# weko.net
KiCad netlist of a schematic drawn in EAGLE
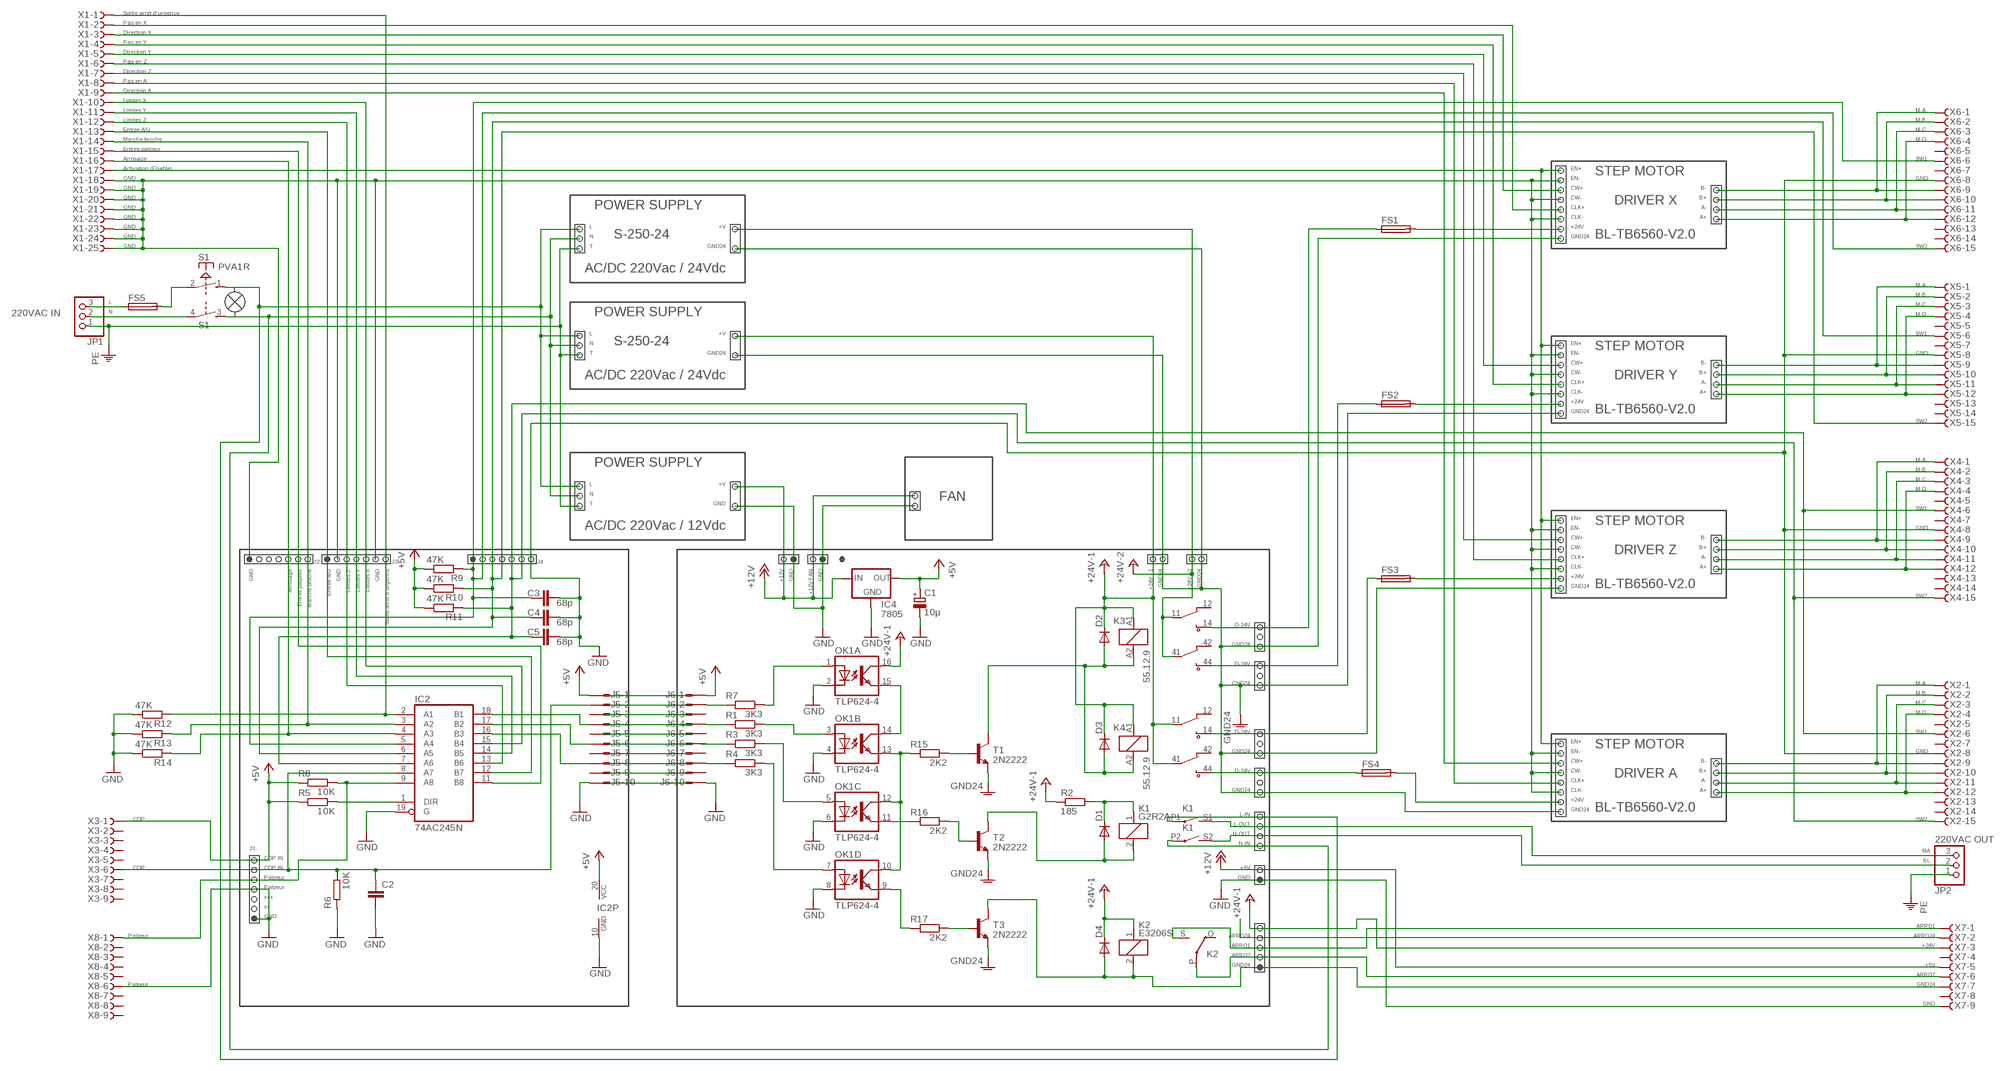
[diagram p0: schematic, sheet 1]

(export (version "E")
  (design (tool "Eeschema 10.0.6"))
  (components
    (comp (ref "C1")
      (value "10µ")
      (footprint "eagle-import:E2-4")
      (libsource (lib "eagle-import") (part "CPOL-EUE2-4"))
    )
    (comp (ref "C2")
      (value "C-EU050-030X075")
      (footprint "eagle-import:C050-030X075")
      (libsource (lib "eagle-import") (part "C-EU050-030X075"))
    )
    (comp (ref "C3")
      (value "68p")
      (footprint "eagle-import:C050-030X075")
      (libsource (lib "eagle-import") (part "C-EU050-030X075"))
    )
    (comp (ref "C4")
      (value "68p")
      (footprint "eagle-import:C050-030X075")
      (libsource (lib "eagle-import") (part "C-EU050-030X075"))
    )
    (comp (ref "C5")
      (value "68p")
      (footprint "eagle-import:C050-030X075")
      (libsource (lib "eagle-import") (part "C-EU050-030X075"))
    )
    (comp (ref "D1")
      (value "1N4148DO35-10")
      (footprint "eagle-import:DO35-10")
      (libsource (lib "eagle-import") (part "1N4148DO35-10"))
    )
    (comp (ref "D2")
      (value "1N4148DO35-10")
      (footprint "eagle-import:DO35-10")
      (libsource (lib "eagle-import") (part "1N4148DO35-10"))
    )
    (comp (ref "D3")
      (value "1N4148DO35-10")
      (footprint "eagle-import:DO35-10")
      (libsource (lib "eagle-import") (part "1N4148DO35-10"))
    )
    (comp (ref "D4")
      (value "1N4148DO35-10")
      (footprint "eagle-import:DO35-10")
      (libsource (lib "eagle-import") (part "1N4148DO35-10"))
    )
    (comp (ref "FS1")
      (value "KS10H")
      (footprint "eagle-import:KS10H")
      (libsource (lib "eagle-import") (part "KS10H"))
    )
    (comp (ref "FS2")
      (value "KS10H")
      (footprint "eagle-import:KS10H")
      (libsource (lib "eagle-import") (part "KS10H"))
    )
    (comp (ref "FS3")
      (value "KS10H")
      (footprint "eagle-import:KS10H")
      (libsource (lib "eagle-import") (part "KS10H"))
    )
    (comp (ref "FS4")
      (value "KS10H")
      (footprint "eagle-import:KS10H")
      (libsource (lib "eagle-import") (part "KS10H"))
    )
    (comp (ref "FS5")
      (value "KS10H")
      (footprint "eagle-import:KS10H")
      (libsource (lib "eagle-import") (part "KS10H"))
    )
    (comp (ref "IC2")
      (value "74AC245N")
      (footprint "eagle-import:DIL20")
      (libsource (lib "eagle-import") (part "74245NAC"))
    )
    (comp (ref "IC4")
      (value "7805")
      (footprint "eagle-import:78MXXS")
      (libsource (lib "eagle-import") (part "78MXXS"))
    )
    (comp (ref "J5")
      (value "10HS")
      (footprint "eagle-import:10H")
      (libsource (lib "eagle-import") (part "10HS"))
    )
    (comp (ref "J6")
      (value "10HS")
      (footprint "eagle-import:10H")
      (libsource (lib "eagle-import") (part "10HS"))
    )
    (comp (ref "JP1")
      (value "PINHD-1X03_2.00")
      (footprint "eagle-import:1X03M")
      (libsource (lib "eagle-import") (part "PINHD-1X03_2.00"))
    )
    (comp (ref "JP2")
      (value "PINHD-1X03_2.00")
      (footprint "eagle-import:1X03M")
      (libsource (lib "eagle-import") (part "PINHD-1X03_2.00"))
    )
    (comp (ref "K1")
      (value "G2R2A")
      (footprint "eagle-import:G2R2A")
      (fields (field (name "MPN") "G2R-2A-DC24"))
      (libsource (lib "eagle-import") (part "G2R2A"))
    )
    (comp (ref "K2")
      (value "E3206S")
      (footprint "eagle-import:E3206S")
      (libsource (lib "eagle-import") (part "E3206S"))
    )
    (comp (ref "K3")
      (value "55.12.9")
      (footprint "eagle-import:55.12")
      (libsource (lib "eagle-import") (part "55.12.8"))
    )
    (comp (ref "K4")
      (value "55.12.9")
      (footprint "eagle-import:55.12")
      (libsource (lib "eagle-import") (part "55.12.8"))
    )
    (comp (ref "OK1")
      (value "TLP624-4")
      (footprint "eagle-import:MINI-FLAT-16")
      (libsource (lib "eagle-import") (part "TLP283-4"))
    )
    (comp (ref "R1")
      (value "3K3")
      (footprint "eagle-import:0411_12")
      (libsource (lib "eagle-import") (part "R-EU_0411/12"))
    )
    (comp (ref "R2")
      (value "185")
      (footprint "eagle-import:0411_12")
      (libsource (lib "eagle-import") (part "R-EU_0411/12"))
    )
    (comp (ref "R3")
      (value "3K3")
      (footprint "eagle-import:0411_12")
      (libsource (lib "eagle-import") (part "R-EU_0411/12"))
    )
    (comp (ref "R4")
      (value "3K3")
      (footprint "eagle-import:0411_12")
      (libsource (lib "eagle-import") (part "R-EU_0411/12"))
    )
    (comp (ref "R5")
      (value "10K")
      (footprint "eagle-import:0411_12")
      (libsource (lib "eagle-import") (part "R-EU_0411/12"))
    )
    (comp (ref "R6")
      (value "10K")
      (footprint "eagle-import:0411_12")
      (libsource (lib "eagle-import") (part "R-EU_0411/12"))
    )
    (comp (ref "R7")
      (value "3K3")
      (footprint "eagle-import:0411_12")
      (libsource (lib "eagle-import") (part "R-EU_0411/12"))
    )
    (comp (ref "R8")
      (value "10K")
      (footprint "eagle-import:0411_12")
      (libsource (lib "eagle-import") (part "R-EU_0411/12"))
    )
    (comp (ref "R9")
      (value "47K")
      (footprint "eagle-import:0411_12")
      (libsource (lib "eagle-import") (part "R-EU_0411/12"))
    )
    (comp (ref "R10")
      (value "47K")
      (footprint "eagle-import:0411_12")
      (libsource (lib "eagle-import") (part "R-EU_0411/12"))
    )
    (comp (ref "R11")
      (value "47K")
      (footprint "eagle-import:0411_12")
      (libsource (lib "eagle-import") (part "R-EU_0411/12"))
    )
    (comp (ref "R12")
      (value "47K")
      (footprint "eagle-import:0411_12")
      (libsource (lib "eagle-import") (part "R-EU_0411/12"))
    )
    (comp (ref "R13")
      (value "47K")
      (footprint "eagle-import:0411_12")
      (libsource (lib "eagle-import") (part "R-EU_0411/12"))
    )
    (comp (ref "R14")
      (value "47K")
      (footprint "eagle-import:0411_12")
      (libsource (lib "eagle-import") (part "R-EU_0411/12"))
    )
    (comp (ref "R15")
      (value "2K2")
      (footprint "eagle-import:0411_12")
      (libsource (lib "eagle-import") (part "R-EU_0411/12"))
    )
    (comp (ref "R16")
      (value "2K2")
      (footprint "eagle-import:0411_12")
      (libsource (lib "eagle-import") (part "R-EU_0411/12"))
    )
    (comp (ref "R17")
      (value "2K2")
      (footprint "eagle-import:0411_12")
      (libsource (lib "eagle-import") (part "R-EU_0411/12"))
    )
    (comp (ref "S1")
      (value "PVA1R")
      (footprint "eagle-import:PVA1R")
      (libsource (lib "eagle-import") (part "PVA1R"))
    )
    (comp (ref "T1")
      (value "2N2222")
      (footprint "eagle-import:TO18")
      (libsource (lib "eagle-import") (part "2N2222"))
    )
    (comp (ref "T2")
      (value "2N2222")
      (footprint "eagle-import:TO18")
      (libsource (lib "eagle-import") (part "2N2222"))
    )
    (comp (ref "T3")
      (value "2N2222")
      (footprint "eagle-import:TO18")
      (libsource (lib "eagle-import") (part "2N2222"))
    )
    (comp (ref "X1")
      (value "F25VBS")
      (footprint "eagle-import:F25VB")
      (libsource (lib "eagle-import") (part "F25?SVB"))
    )
    (comp (ref "X2")
      (value "F15VBS")
      (footprint "eagle-import:F15VB")
      (libsource (lib "eagle-import") (part "F15?SVB"))
    )
    (comp (ref "X3")
      (value "F09VBS")
      (footprint "eagle-import:F09VB")
      (libsource (lib "eagle-import") (part "F09?SVB"))
    )
    (comp (ref "X4")
      (value "F15VBS")
      (footprint "eagle-import:F15VB")
      (libsource (lib "eagle-import") (part "F15?SVB"))
    )
    (comp (ref "X5")
      (value "F15VBS")
      (footprint "eagle-import:F15VB")
      (libsource (lib "eagle-import") (part "F15?SVB"))
    )
    (comp (ref "X6")
      (value "F15VBS")
      (footprint "eagle-import:F15VB")
      (libsource (lib "eagle-import") (part "F15?SVB"))
    )
    (comp (ref "X7")
      (value "F09VBS")
      (footprint "eagle-import:F09VB")
      (libsource (lib "eagle-import") (part "F09?SVB"))
    )
    (comp (ref "X8")
      (value "F09VBS")
      (footprint "eagle-import:F09VB")
      (libsource (lib "eagle-import") (part "F09?SVB"))
    )
  )
  (nets
    (net (code "1") (name "+5V") (class "Default")
      (node (ref "C1") (pin "+") (pinfunction "+_+") (pintype "passive"))
      (node (ref "IC2") (pin "20") (pinfunction "VCC_20") (pintype "power_in"))
      (node (ref "IC4") (pin "OUT") (pinfunction "OUT_OUT") (pintype "passive"))
      (node (ref "J5") (pin "1") (pinfunction "S_1") (pintype "passive"))
      (node (ref "J6") (pin "1") (pinfunction "S_1") (pintype "passive"))
      (node (ref "R10") (pin "1") (pinfunction "1_1") (pintype "passive"))
      (node (ref "R11") (pin "1") (pinfunction "1_1") (pintype "passive"))
      (node (ref "R5") (pin "2") (pinfunction "2_2") (pintype "passive"))
      (node (ref "R8") (pin "2") (pinfunction "2_2") (pintype "passive"))
      (node (ref "R9") (pin "1") (pinfunction "1_1") (pintype "passive"))
      (node (ref "X3") (pin "1") (pinfunction "F_1") (pintype "passive"))
    )
    (net (code "2") (name "+12V") (class "Default")
      (node (ref "IC4") (pin "IN") (pinfunction "IN_IN") (pintype "input"))
      (node (ref "X7") (pin "5") (pinfunction "F_5") (pintype "passive"))
    )
    (net (code "3") (name "+24V-1") (class "Default")
      (node (ref "D2") (pin "C") (pinfunction "C_C") (pintype "passive"))
      (node (ref "D3") (pin "C") (pinfunction "C_C") (pintype "passive"))
      (node (ref "D4") (pin "C") (pinfunction "C_C") (pintype "passive"))
      (node (ref "K2") (pin "1") (pinfunction "1_1") (pintype "passive"))
      (node (ref "K3") (pin "11") (pinfunction "9_11") (pintype "passive"))
      (node (ref "K3") (pin "41") (pinfunction "12_41") (pintype "passive"))
      (node (ref "K3") (pin "A1") (pinfunction "A1_A1") (pintype "passive"))
      (node (ref "K4") (pin "11") (pinfunction "9_11") (pintype "passive"))
      (node (ref "K4") (pin "41") (pinfunction "12_41") (pintype "passive"))
      (node (ref "K4") (pin "A1") (pinfunction "A1_A1") (pintype "passive"))
      (node (ref "OK1") (pin "16") (pinfunction "COL_16") (pintype "passive"))
      (node (ref "R2") (pin "1") (pinfunction "1_1") (pintype "passive"))
      (node (ref "X7") (pin "3") (pinfunction "F_3") (pintype "passive"))
    )
    (net (code "4") (name "GND") (class "Default")
      (node (ref "C1") (pin "-") (pinfunction "-_-") (pintype "passive"))
      (node (ref "C2") (pin "2") (pinfunction "2_2") (pintype "passive"))
      (node (ref "C3") (pin "2") (pinfunction "2_2") (pintype "passive"))
      (node (ref "C4") (pin "2") (pinfunction "2_2") (pintype "passive"))
      (node (ref "C5") (pin "2") (pinfunction "2_2") (pintype "passive"))
      (node (ref "IC2") (pin "10") (pinfunction "GND_10") (pintype "power_in"))
      (node (ref "IC2") (pin "19") (pinfunction "G_19") (pintype "input"))
      (node (ref "IC4") (pin "GND") (pinfunction "GND_GND") (pintype "input"))
      (node (ref "J5") (pin "10") (pinfunction "S_10") (pintype "passive"))
      (node (ref "J6") (pin "10") (pinfunction "S_10") (pintype "passive"))
      (node (ref "OK1") (pin "2") (pinfunction "C_2") (pintype "passive"))
      (node (ref "OK1") (pin "4") (pinfunction "C_4") (pintype "passive"))
      (node (ref "OK1") (pin "6") (pinfunction "C_6") (pintype "passive"))
      (node (ref "OK1") (pin "8") (pinfunction "C_8") (pintype "passive"))
      (node (ref "R12") (pin "1") (pinfunction "1_1") (pintype "passive"))
      (node (ref "R13") (pin "1") (pinfunction "1_1") (pintype "passive"))
      (node (ref "R14") (pin "1") (pinfunction "1_1") (pintype "passive"))
      (node (ref "R6") (pin "2") (pinfunction "2_2") (pintype "passive"))
      (node (ref "X2") (pin "8") (pinfunction "F_8") (pintype "passive"))
      (node (ref "X4") (pin "8") (pinfunction "F_8") (pintype "passive"))
      (node (ref "X5") (pin "8") (pinfunction "F_8") (pintype "passive"))
      (node (ref "X6") (pin "8") (pinfunction "F_8") (pintype "passive"))
      (node (ref "X7") (pin "9") (pinfunction "F_9") (pintype "passive"))
      (node (ref "X8") (pin "6") (pinfunction "F_6") (pintype "passive"))
    )
    (net (code "5") (name "GND24") (class "Default")
      (node (ref "T1") (pin "1") (pinfunction "E_1") (pintype "passive"))
      (node (ref "T2") (pin "1") (pinfunction "E_1") (pintype "passive"))
      (node (ref "T3") (pin "1") (pinfunction "E_1") (pintype "passive"))
    )
    (net (code "6") (name "Net-(D1-PadC)") (class "Default")
      (node (ref "D1") (pin "C") (pinfunction "C_C") (pintype "passive"))
      (node (ref "K1") (pin "1") (pinfunction "1_1") (pintype "passive"))
      (node (ref "R2") (pin "2") (pinfunction "2_2") (pintype "passive"))
    )
    (net (code "7") (name "Net-(FS5-Pad1)") (class "Default")
      (node (ref "FS5") (pin "1") (pinfunction "1_1") (pintype "passive"))
      (node (ref "JP1") (pin "3") (pinfunction "3_3") (pintype "passive"))
    )
    (net (code "8") (name "Net-(IC2A-A1)") (class "Default")
      (node (ref "IC2") (pin "2") (pinfunction "A1_2") (pintype "bidirectional"))
      (node (ref "R12") (pin "2") (pinfunction "2_2") (pintype "passive"))
      (node (ref "X1") (pin "1") (pinfunction "F_1") (pintype "passive"))
    )
    (net (code "9") (name "Net-(IC2A-A2)") (class "Default")
      (node (ref "IC2") (pin "3") (pinfunction "A2_3") (pintype "bidirectional"))
      (node (ref "R13") (pin "2") (pinfunction "2_2") (pintype "passive"))
      (node (ref "X1") (pin "14") (pinfunction "F_14") (pintype "passive"))
    )
    (net (code "10") (name "Net-(IC2A-A3)") (class "Default")
      (node (ref "IC2") (pin "4") (pinfunction "A3_4") (pintype "bidirectional"))
      (node (ref "R14") (pin "2") (pinfunction "2_2") (pintype "passive"))
      (node (ref "X1") (pin "16") (pinfunction "F_16") (pintype "passive"))
    )
    (net (code "11") (name "Net-(IC2A-A4)") (class "Default")
      (node (ref "C3") (pin "1") (pinfunction "1_1") (pintype "passive"))
      (node (ref "IC2") (pin "5") (pinfunction "A4_5") (pintype "bidirectional"))
      (node (ref "R9") (pin "2") (pinfunction "2_2") (pintype "passive"))
      (node (ref "X6") (pin "15") (pinfunction "F_15") (pintype "passive"))
      (node (ref "X6") (pin "6") (pinfunction "F_6") (pintype "passive"))
    )
    (net (code "12") (name "Net-(IC2A-A5)") (class "Default")
      (node (ref "C4") (pin "1") (pinfunction "1_1") (pintype "passive"))
      (node (ref "IC2") (pin "6") (pinfunction "A5_6") (pintype "bidirectional"))
      (node (ref "R10") (pin "2") (pinfunction "2_2") (pintype "passive"))
      (node (ref "X5") (pin "15") (pinfunction "F_15") (pintype "passive"))
      (node (ref "X5") (pin "6") (pinfunction "F_6") (pintype "passive"))
    )
    (net (code "13") (name "Net-(IC2A-A6)") (class "Default")
      (node (ref "C5") (pin "1") (pinfunction "1_1") (pintype "passive"))
      (node (ref "IC2") (pin "7") (pinfunction "A6_7") (pintype "bidirectional"))
      (node (ref "R11") (pin "2") (pinfunction "2_2") (pintype "passive"))
      (node (ref "X2") (pin "15") (pinfunction "F_15") (pintype "passive"))
      (node (ref "X2") (pin "6") (pinfunction "F_6") (pintype "passive"))
      (node (ref "X4") (pin "15") (pinfunction "F_15") (pintype "passive"))
      (node (ref "X4") (pin "6") (pinfunction "F_6") (pintype "passive"))
    )
    (net (code "14") (name "Net-(IC2A-A7)") (class "Default")
      (node (ref "C2") (pin "1") (pinfunction "1_1") (pintype "passive"))
      (node (ref "IC2") (pin "8") (pinfunction "A7_8") (pintype "bidirectional"))
      (node (ref "J5") (pin "2") (pinfunction "S_2") (pintype "passive"))
      (node (ref "R6") (pin "1") (pinfunction "1_1") (pintype "passive"))
      (node (ref "X3") (pin "6") (pinfunction "F_6") (pintype "passive"))
    )
    (net (code "15") (name "Net-(IC2A-A8)") (class "Default")
      (node (ref "IC2") (pin "9") (pinfunction "A8_9") (pintype "bidirectional"))
      (node (ref "R8") (pin "1") (pinfunction "1_1") (pintype "passive"))
      (node (ref "X8") (pin "1") (pinfunction "F_1") (pintype "passive"))
    )
    (net (code "16") (name "Net-(IC2A-B1)") (class "Default")
      (node (ref "IC2") (pin "18") (pinfunction "B1_18") (pintype "bidirectional"))
      (node (ref "J5") (pin "4") (pinfunction "S_4") (pintype "passive"))
    )
    (net (code "17") (name "Net-(IC2A-B2)") (class "Default")
      (node (ref "IC2") (pin "17") (pinfunction "B2_17") (pintype "bidirectional"))
      (node (ref "J5") (pin "6") (pinfunction "S_6") (pintype "passive"))
    )
    (net (code "18") (name "Net-(IC2A-B3)") (class "Default")
      (node (ref "IC2") (pin "16") (pinfunction "B3_16") (pintype "bidirectional"))
      (node (ref "J5") (pin "8") (pinfunction "S_8") (pintype "passive"))
    )
    (net (code "19") (name "Net-(IC2A-B4)") (class "Default")
      (node (ref "IC2") (pin "15") (pinfunction "B4_15") (pintype "bidirectional"))
      (node (ref "X1") (pin "10") (pinfunction "F_10") (pintype "passive"))
    )
    (net (code "20") (name "Net-(IC2A-B5)") (class "Default")
      (node (ref "IC2") (pin "14") (pinfunction "B5_14") (pintype "bidirectional"))
      (node (ref "X1") (pin "11") (pinfunction "F_11") (pintype "passive"))
    )
    (net (code "21") (name "Net-(IC2A-B6)") (class "Default")
      (node (ref "IC2") (pin "13") (pinfunction "B6_13") (pintype "bidirectional"))
      (node (ref "X1") (pin "12") (pinfunction "F_12") (pintype "passive"))
    )
    (net (code "22") (name "Net-(IC2A-B7)") (class "Default")
      (node (ref "IC2") (pin "12") (pinfunction "B7_12") (pintype "bidirectional"))
      (node (ref "X1") (pin "13") (pinfunction "F_13") (pintype "passive"))
    )
    (net (code "23") (name "Net-(IC2A-B8)") (class "Default")
      (node (ref "IC2") (pin "11") (pinfunction "B8_11") (pintype "bidirectional"))
      (node (ref "X1") (pin "15") (pinfunction "F_15") (pintype "passive"))
    )
    (net (code "24") (name "Net-(IC2A-DIR)") (class "Default")
      (node (ref "IC2") (pin "1") (pinfunction "DIR_1") (pintype "input"))
      (node (ref "R5") (pin "1") (pinfunction "1_1") (pintype "passive"))
    )
    (net (code "25") (name "Net-(J6C-S)") (class "Default")
      (node (ref "J6") (pin "2") (pinfunction "S_2") (pintype "passive"))
      (node (ref "R7") (pin "2") (pinfunction "2_2") (pintype "passive"))
    )
    (net (code "26") (name "Net-(J6E-S)") (class "Default")
      (node (ref "J6") (pin "4") (pinfunction "S_4") (pintype "passive"))
      (node (ref "R1") (pin "2") (pinfunction "2_2") (pintype "passive"))
    )
    (net (code "27") (name "Net-(J6I-S)") (class "Default")
      (node (ref "J6") (pin "8") (pinfunction "S_8") (pintype "passive"))
      (node (ref "R4") (pin "2") (pinfunction "2_2") (pintype "passive"))
    )
    (net (code "28") (name "Net-(K1B-P)") (class "Default")
      (node (ref "K1") (pin "P1") (pinfunction "P_P1") (pintype "passive"))
      (node (ref "S1") (pin "1") (pinfunction "S_1") (pintype "passive"))
    )
    (net (code "29") (name "Net-(K1B-S)") (class "Default")
      (node (ref "JP2") (pin "3") (pinfunction "3_3") (pintype "passive"))
      (node (ref "K1") (pin "S1") (pinfunction "S_S1") (pintype "passive"))
    )
    (net (code "30") (name "Net-(K1C-P)") (class "Default")
      (node (ref "K1") (pin "P2") (pinfunction "P_P2") (pintype "passive"))
      (node (ref "S1") (pin "3") (pinfunction "S_3") (pintype "passive"))
    )
    (net (code "31") (name "Net-(K1C-S)") (class "Default")
      (node (ref "JP2") (pin "2") (pinfunction "2_2") (pintype "passive"))
      (node (ref "K1") (pin "S2") (pinfunction "S_S2") (pintype "passive"))
    )
    (net (code "32") (name "Net-(K3-5)") (class "Default")
      (node (ref "FS1") (pin "1") (pinfunction "1_1") (pintype "passive"))
      (node (ref "K3") (pin "14") (pinfunction "5_14") (pintype "passive"))
    )
    (net (code "33") (name "Net-(K3-8)") (class "Default")
      (node (ref "FS2") (pin "1") (pinfunction "1_1") (pintype "passive"))
      (node (ref "K3") (pin "44") (pinfunction "8_44") (pintype "passive"))
    )
    (net (code "34") (name "Net-(K4-5)") (class "Default")
      (node (ref "FS3") (pin "1") (pinfunction "1_1") (pintype "passive"))
      (node (ref "K4") (pin "14") (pinfunction "5_14") (pintype "passive"))
    )
    (net (code "35") (name "Net-(K4-8)") (class "Default")
      (node (ref "FS4") (pin "1") (pinfunction "1_1") (pintype "passive"))
      (node (ref "K4") (pin "44") (pinfunction "8_44") (pintype "passive"))
    )
    (net (code "36") (name "Net-(OK1A-A)") (class "Default")
      (node (ref "OK1") (pin "1") (pinfunction "A_1") (pintype "passive"))
      (node (ref "R7") (pin "1") (pinfunction "1_1") (pintype "passive"))
    )
    (net (code "37") (name "Net-(OK1A-EMIT)") (class "Default")
      (node (ref "OK1") (pin "14") (pinfunction "COL_14") (pintype "passive"))
      (node (ref "OK1") (pin "15") (pinfunction "EMIT_15") (pintype "passive"))
    )
    (net (code "38") (name "Net-(OK1B-A)") (class "Default")
      (node (ref "OK1") (pin "3") (pinfunction "A_3") (pintype "passive"))
      (node (ref "R1") (pin "1") (pinfunction "1_1") (pintype "passive"))
    )
    (net (code "39") (name "Net-(OK1B-EMIT)") (class "Default")
      (node (ref "OK1") (pin "10") (pinfunction "COL_10") (pintype "passive"))
      (node (ref "OK1") (pin "12") (pinfunction "COL_12") (pintype "passive"))
      (node (ref "OK1") (pin "13") (pinfunction "EMIT_13") (pintype "passive"))
      (node (ref "R15") (pin "2") (pinfunction "2_2") (pintype "passive"))
    )
    (net (code "40") (name "Net-(OK1C-A)") (class "Default")
      (node (ref "OK1") (pin "5") (pinfunction "A_5") (pintype "passive"))
      (node (ref "R3") (pin "1") (pinfunction "1_1") (pintype "passive"))
    )
    (net (code "41") (name "Net-(OK1C-EMIT)") (class "Default")
      (node (ref "OK1") (pin "11") (pinfunction "EMIT_11") (pintype "passive"))
      (node (ref "R16") (pin "2") (pinfunction "2_2") (pintype "passive"))
    )
    (net (code "42") (name "Net-(OK1D-A)") (class "Default")
      (node (ref "OK1") (pin "7") (pinfunction "A_7") (pintype "passive"))
      (node (ref "R4") (pin "1") (pinfunction "1_1") (pintype "passive"))
    )
    (net (code "43") (name "Net-(OK1D-EMIT)") (class "Default")
      (node (ref "OK1") (pin "9") (pinfunction "EMIT_9") (pintype "passive"))
      (node (ref "R17") (pin "2") (pinfunction "2_2") (pintype "passive"))
    )
    (net (code "44") (name "Net-(S1A-P)") (class "Default")
      (node (ref "FS5") (pin "2") (pinfunction "2_2") (pintype "passive"))
      (node (ref "S1") (pin "2") (pinfunction "P_2") (pintype "passive"))
    )
    (net (code "45") (name "Net-(S1B-P)") (class "Default")
      (node (ref "JP1") (pin "2") (pinfunction "2_2") (pintype "passive"))
      (node (ref "S1") (pin "4") (pinfunction "P_4") (pintype "passive"))
    )
    (net (code "46") (name "Net-(T1-B)") (class "Default")
      (node (ref "R15") (pin "1") (pinfunction "1_1") (pintype "passive"))
      (node (ref "T1") (pin "2") (pinfunction "B_2") (pintype "passive"))
    )
    (net (code "47") (name "Net-(T1-C)") (class "Default")
      (node (ref "D2") (pin "A") (pinfunction "A_A") (pintype "passive"))
      (node (ref "D3") (pin "A") (pinfunction "A_A") (pintype "passive"))
      (node (ref "K3") (pin "A2") (pinfunction "A2_A2") (pintype "passive"))
      (node (ref "K4") (pin "A2") (pinfunction "A2_A2") (pintype "passive"))
      (node (ref "T1") (pin "3") (pinfunction "C_3") (pintype "passive"))
    )
    (net (code "48") (name "Net-(T2-B)") (class "Default")
      (node (ref "R16") (pin "1") (pinfunction "1_1") (pintype "passive"))
      (node (ref "T2") (pin "2") (pinfunction "B_2") (pintype "passive"))
    )
    (net (code "49") (name "Net-(T2-C)") (class "Default")
      (node (ref "D1") (pin "A") (pinfunction "A_A") (pintype "passive"))
      (node (ref "K1") (pin "2") (pinfunction "2_2") (pintype "passive"))
      (node (ref "T2") (pin "3") (pinfunction "C_3") (pintype "passive"))
    )
    (net (code "50") (name "Net-(T3-B)") (class "Default")
      (node (ref "R17") (pin "1") (pinfunction "1_1") (pintype "passive"))
      (node (ref "T3") (pin "2") (pinfunction "B_2") (pintype "passive"))
    )
    (net (code "51") (name "Net-(T3-C)") (class "Default")
      (node (ref "D4") (pin "A") (pinfunction "A_A") (pintype "passive"))
      (node (ref "K2") (pin "2") (pinfunction "2_2") (pintype "passive"))
      (node (ref "T3") (pin "3") (pinfunction "C_3") (pintype "passive"))
      (node (ref "X7") (pin "7") (pinfunction "F_7") (pintype "passive"))
    )
    (net (code "52") (name "Net-(X1J-F)") (class "Default")
      (node (ref "X1") (pin "18") (pinfunction "F_18") (pintype "passive"))
      (node (ref "X1") (pin "19") (pinfunction "F_19") (pintype "passive"))
      (node (ref "X1") (pin "20") (pinfunction "F_20") (pintype "passive"))
      (node (ref "X1") (pin "21") (pinfunction "F_21") (pintype "passive"))
      (node (ref "X1") (pin "22") (pinfunction "F_22") (pintype "passive"))
      (node (ref "X1") (pin "23") (pinfunction "F_23") (pintype "passive"))
      (node (ref "X1") (pin "24") (pinfunction "F_24") (pintype "passive"))
      (node (ref "X1") (pin "25") (pinfunction "F_25") (pintype "passive"))
    )
    (net (code "53") (name "Net-(X2A-F)") (class "Default")
      (node (ref "X2") (pin "1") (pinfunction "F_1") (pintype "passive"))
      (node (ref "X2") (pin "9") (pinfunction "F_9") (pintype "passive"))
    )
    (net (code "54") (name "Net-(X2B-F)") (class "Default")
      (node (ref "X2") (pin "10") (pinfunction "F_10") (pintype "passive"))
      (node (ref "X2") (pin "2") (pinfunction "F_2") (pintype "passive"))
    )
    (net (code "55") (name "Net-(X2C-F)") (class "Default")
      (node (ref "X2") (pin "11") (pinfunction "F_11") (pintype "passive"))
      (node (ref "X2") (pin "3") (pinfunction "F_3") (pintype "passive"))
    )
    (net (code "56") (name "Net-(X2D-F)") (class "Default")
      (node (ref "X2") (pin "12") (pinfunction "F_12") (pintype "passive"))
      (node (ref "X2") (pin "4") (pinfunction "F_4") (pintype "passive"))
    )
    (net (code "57") (name "Net-(X4A-F)") (class "Default")
      (node (ref "X4") (pin "1") (pinfunction "F_1") (pintype "passive"))
      (node (ref "X4") (pin "9") (pinfunction "F_9") (pintype "passive"))
    )
    (net (code "58") (name "Net-(X4B-F)") (class "Default")
      (node (ref "X4") (pin "10") (pinfunction "F_10") (pintype "passive"))
      (node (ref "X4") (pin "2") (pinfunction "F_2") (pintype "passive"))
    )
    (net (code "59") (name "Net-(X4C-F)") (class "Default")
      (node (ref "X4") (pin "11") (pinfunction "F_11") (pintype "passive"))
      (node (ref "X4") (pin "3") (pinfunction "F_3") (pintype "passive"))
    )
    (net (code "60") (name "Net-(X4D-F)") (class "Default")
      (node (ref "X4") (pin "12") (pinfunction "F_12") (pintype "passive"))
      (node (ref "X4") (pin "4") (pinfunction "F_4") (pintype "passive"))
    )
    (net (code "61") (name "Net-(X5A-F)") (class "Default")
      (node (ref "X5") (pin "1") (pinfunction "F_1") (pintype "passive"))
      (node (ref "X5") (pin "9") (pinfunction "F_9") (pintype "passive"))
    )
    (net (code "62") (name "Net-(X5B-F)") (class "Default")
      (node (ref "X5") (pin "10") (pinfunction "F_10") (pintype "passive"))
      (node (ref "X5") (pin "2") (pinfunction "F_2") (pintype "passive"))
    )
    (net (code "63") (name "Net-(X5C-F)") (class "Default")
      (node (ref "X5") (pin "11") (pinfunction "F_11") (pintype "passive"))
      (node (ref "X5") (pin "3") (pinfunction "F_3") (pintype "passive"))
    )
    (net (code "64") (name "Net-(X5D-F)") (class "Default")
      (node (ref "X5") (pin "12") (pinfunction "F_12") (pintype "passive"))
      (node (ref "X5") (pin "4") (pinfunction "F_4") (pintype "passive"))
    )
    (net (code "65") (name "Net-(X6A-F)") (class "Default")
      (node (ref "X6") (pin "1") (pinfunction "F_1") (pintype "passive"))
      (node (ref "X6") (pin "9") (pinfunction "F_9") (pintype "passive"))
    )
    (net (code "66") (name "Net-(X6B-F)") (class "Default")
      (node (ref "X6") (pin "10") (pinfunction "F_10") (pintype "passive"))
      (node (ref "X6") (pin "2") (pinfunction "F_2") (pintype "passive"))
    )
    (net (code "67") (name "Net-(X6C-F)") (class "Default")
      (node (ref "X6") (pin "11") (pinfunction "F_11") (pintype "passive"))
      (node (ref "X6") (pin "3") (pinfunction "F_3") (pintype "passive"))
    )
    (net (code "68") (name "Net-(X6D-F)") (class "Default")
      (node (ref "X6") (pin "12") (pinfunction "F_12") (pintype "passive"))
      (node (ref "X6") (pin "4") (pinfunction "F_4") (pintype "passive"))
    )
    (net (code "69") (name "Net-(X7A-F)") (class "Default")
      (node (ref "K2") (pin "S") (pinfunction "S_S") (pintype "passive"))
      (node (ref "X7") (pin "1") (pinfunction "F_1") (pintype "passive"))
    )
    (net (code "70") (name "Net-(X7F-F)") (class "Default")
      (node (ref "K2") (pin "P") (pinfunction "P_P") (pintype "passive"))
      (node (ref "X7") (pin "6") (pinfunction "F_6") (pintype "passive"))
    )
    (net (code "71") (name "PE") (class "Default")
      (node (ref "JP1") (pin "1") (pinfunction "1_1") (pintype "passive"))
      (node (ref "JP2") (pin "1") (pinfunction "1_1") (pintype "passive"))
    )
    (net (code "72") (name "unconnected-(FS1-Pad2)") (class "Default")
      (node (ref "FS1") (pin "2") (pinfunction "2_2") (pintype "passive"))
    )
    (net (code "73") (name "unconnected-(FS2-Pad2)") (class "Default")
      (node (ref "FS2") (pin "2") (pinfunction "2_2") (pintype "passive"))
    )
    (net (code "74") (name "unconnected-(FS3-Pad2)") (class "Default")
      (node (ref "FS3") (pin "2") (pinfunction "2_2") (pintype "passive"))
    )
    (net (code "75") (name "unconnected-(FS4-Pad2)") (class "Default")
      (node (ref "FS4") (pin "2") (pinfunction "2_2") (pintype "passive"))
    )
    (net (code "76") (name "unconnected-(J5D-S-Pad3)") (class "Default")
      (node (ref "J5") (pin "3") (pinfunction "S_3") (pintype "passive"))
    )
    (net (code "77") (name "unconnected-(J5F-S-Pad5)") (class "Default")
      (node (ref "J5") (pin "5") (pinfunction "S_5") (pintype "passive"))
    )
    (net (code "78") (name "unconnected-(J5H-S-Pad7)") (class "Default")
      (node (ref "J5") (pin "7") (pinfunction "S_7") (pintype "passive"))
    )
    (net (code "79") (name "unconnected-(J5J-S-Pad9)") (class "Default")
      (node (ref "J5") (pin "9") (pinfunction "S_9") (pintype "passive"))
    )
    (net (code "80") (name "unconnected-(J6D-S-Pad3)") (class "Default")
      (node (ref "J6") (pin "3") (pinfunction "S_3") (pintype "passive"))
    )
    (net (code "81") (name "unconnected-(J6F-S-Pad5)") (class "Default")
      (node (ref "J6") (pin "5") (pinfunction "S_5") (pintype "passive"))
    )
    (net (code "82") (name "unconnected-(J6G-S-Pad6)") (class "Default")
      (node (ref "J6") (pin "6") (pinfunction "S_6") (pintype "passive"))
    )
    (net (code "83") (name "unconnected-(J6H-S-Pad7)") (class "Default")
      (node (ref "J6") (pin "7") (pinfunction "S_7") (pintype "passive"))
    )
    (net (code "84") (name "unconnected-(J6J-S-Pad9)") (class "Default")
      (node (ref "J6") (pin "9") (pinfunction "S_9") (pintype "passive"))
    )
    (net (code "85") (name "unconnected-(K2-PadO)") (class "Default")
      (node (ref "K2") (pin "O") (pinfunction "O_O") (pintype "passive"))
    )
    (net (code "86") (name "unconnected-(K3-1-Pad12)") (class "Default")
      (node (ref "K3") (pin "12") (pinfunction "1_12") (pintype "passive"))
    )
    (net (code "87") (name "unconnected-(K3-4-Pad42)") (class "Default")
      (node (ref "K3") (pin "42") (pinfunction "4_42") (pintype "passive"))
    )
    (net (code "88") (name "unconnected-(K4-1-Pad12)") (class "Default")
      (node (ref "K4") (pin "12") (pinfunction "1_12") (pintype "passive"))
    )
    (net (code "89") (name "unconnected-(K4-4-Pad42)") (class "Default")
      (node (ref "K4") (pin "42") (pinfunction "4_42") (pintype "passive"))
    )
    (net (code "90") (name "unconnected-(R3-Pad2)") (class "Default")
      (node (ref "R3") (pin "2") (pinfunction "2_2") (pintype "passive"))
    )
    (net (code "91") (name "unconnected-(X1I-F-Pad17)") (class "Default")
      (node (ref "X1") (pin "17") (pinfunction "F_17") (pintype "passive"))
    )
    (net (code "92") (name "unconnected-(X1L-F-Pad2)") (class "Default")
      (node (ref "X1") (pin "2") (pinfunction "F_2") (pintype "passive"))
    )
    (net (code "93") (name "unconnected-(X1S-F-Pad3)") (class "Default")
      (node (ref "X1") (pin "3") (pinfunction "F_3") (pintype "passive"))
    )
    (net (code "94") (name "unconnected-(X1T-F-Pad4)") (class "Default")
      (node (ref "X1") (pin "4") (pinfunction "F_4") (pintype "passive"))
    )
    (net (code "95") (name "unconnected-(X1U-F-Pad5)") (class "Default")
      (node (ref "X1") (pin "5") (pinfunction "F_5") (pintype "passive"))
    )
    (net (code "96") (name "unconnected-(X1V-F-Pad6)") (class "Default")
      (node (ref "X1") (pin "6") (pinfunction "F_6") (pintype "passive"))
    )
    (net (code "97") (name "unconnected-(X1W-F-Pad7)") (class "Default")
      (node (ref "X1") (pin "7") (pinfunction "F_7") (pintype "passive"))
    )
    (net (code "98") (name "unconnected-(X1X-F-Pad8)") (class "Default")
      (node (ref "X1") (pin "8") (pinfunction "F_8") (pintype "passive"))
    )
    (net (code "99") (name "unconnected-(X1Y-F-Pad9)") (class "Default")
      (node (ref "X1") (pin "9") (pinfunction "F_9") (pintype "passive"))
    )
    (net (code "100") (name "unconnected-(X2E-F-Pad13)") (class "Default")
      (node (ref "X2") (pin "13") (pinfunction "F_13") (pintype "passive"))
    )
    (net (code "101") (name "unconnected-(X2F-F-Pad14)") (class "Default")
      (node (ref "X2") (pin "14") (pinfunction "F_14") (pintype "passive"))
    )
    (net (code "102") (name "unconnected-(X2K-F-Pad5)") (class "Default")
      (node (ref "X2") (pin "5") (pinfunction "F_5") (pintype "passive"))
    )
    (net (code "103") (name "unconnected-(X2M-F-Pad7)") (class "Default")
      (node (ref "X2") (pin "7") (pinfunction "F_7") (pintype "passive"))
    )
    (net (code "104") (name "unconnected-(X3B-F-Pad2)") (class "Default")
      (node (ref "X3") (pin "2") (pinfunction "F_2") (pintype "passive"))
    )
    (net (code "105") (name "unconnected-(X3C-F-Pad3)") (class "Default")
      (node (ref "X3") (pin "3") (pinfunction "F_3") (pintype "passive"))
    )
    (net (code "106") (name "unconnected-(X3D-F-Pad4)") (class "Default")
      (node (ref "X3") (pin "4") (pinfunction "F_4") (pintype "passive"))
    )
    (net (code "107") (name "unconnected-(X3E-F-Pad5)") (class "Default")
      (node (ref "X3") (pin "5") (pinfunction "F_5") (pintype "passive"))
    )
    (net (code "108") (name "unconnected-(X3G-F-Pad7)") (class "Default")
      (node (ref "X3") (pin "7") (pinfunction "F_7") (pintype "passive"))
    )
    (net (code "109") (name "unconnected-(X3H-F-Pad8)") (class "Default")
      (node (ref "X3") (pin "8") (pinfunction "F_8") (pintype "passive"))
    )
    (net (code "110") (name "unconnected-(X3I-F-Pad9)") (class "Default")
      (node (ref "X3") (pin "9") (pinfunction "F_9") (pintype "passive"))
    )
    (net (code "111") (name "unconnected-(X4E-F-Pad13)") (class "Default")
      (node (ref "X4") (pin "13") (pinfunction "F_13") (pintype "passive"))
    )
    (net (code "112") (name "unconnected-(X4F-F-Pad14)") (class "Default")
      (node (ref "X4") (pin "14") (pinfunction "F_14") (pintype "passive"))
    )
    (net (code "113") (name "unconnected-(X4K-F-Pad5)") (class "Default")
      (node (ref "X4") (pin "5") (pinfunction "F_5") (pintype "passive"))
    )
    (net (code "114") (name "unconnected-(X4M-F-Pad7)") (class "Default")
      (node (ref "X4") (pin "7") (pinfunction "F_7") (pintype "passive"))
    )
    (net (code "115") (name "unconnected-(X5E-F-Pad13)") (class "Default")
      (node (ref "X5") (pin "13") (pinfunction "F_13") (pintype "passive"))
    )
    (net (code "116") (name "unconnected-(X5F-F-Pad14)") (class "Default")
      (node (ref "X5") (pin "14") (pinfunction "F_14") (pintype "passive"))
    )
    (net (code "117") (name "unconnected-(X5K-F-Pad5)") (class "Default")
      (node (ref "X5") (pin "5") (pinfunction "F_5") (pintype "passive"))
    )
    (net (code "118") (name "unconnected-(X5M-F-Pad7)") (class "Default")
      (node (ref "X5") (pin "7") (pinfunction "F_7") (pintype "passive"))
    )
    (net (code "119") (name "unconnected-(X6E-F-Pad13)") (class "Default")
      (node (ref "X6") (pin "13") (pinfunction "F_13") (pintype "passive"))
    )
    (net (code "120") (name "unconnected-(X6F-F-Pad14)") (class "Default")
      (node (ref "X6") (pin "14") (pinfunction "F_14") (pintype "passive"))
    )
    (net (code "121") (name "unconnected-(X6K-F-Pad5)") (class "Default")
      (node (ref "X6") (pin "5") (pinfunction "F_5") (pintype "passive"))
    )
    (net (code "122") (name "unconnected-(X6M-F-Pad7)") (class "Default")
      (node (ref "X6") (pin "7") (pinfunction "F_7") (pintype "passive"))
    )
    (net (code "123") (name "unconnected-(X7B-F-Pad2)") (class "Default")
      (node (ref "X7") (pin "2") (pinfunction "F_2") (pintype "passive"))
    )
    (net (code "124") (name "unconnected-(X7D-F-Pad4)") (class "Default")
      (node (ref "X7") (pin "4") (pinfunction "F_4") (pintype "passive"))
    )
    (net (code "125") (name "unconnected-(X7H-F-Pad8)") (class "Default")
      (node (ref "X7") (pin "8") (pinfunction "F_8") (pintype "passive"))
    )
    (net (code "126") (name "unconnected-(X8B-F-Pad2)") (class "Default")
      (node (ref "X8") (pin "2") (pinfunction "F_2") (pintype "passive"))
    )
    (net (code "127") (name "unconnected-(X8C-F-Pad3)") (class "Default")
      (node (ref "X8") (pin "3") (pinfunction "F_3") (pintype "passive"))
    )
    (net (code "128") (name "unconnected-(X8D-F-Pad4)") (class "Default")
      (node (ref "X8") (pin "4") (pinfunction "F_4") (pintype "passive"))
    )
    (net (code "129") (name "unconnected-(X8E-F-Pad5)") (class "Default")
      (node (ref "X8") (pin "5") (pinfunction "F_5") (pintype "passive"))
    )
    (net (code "130") (name "unconnected-(X8G-F-Pad7)") (class "Default")
      (node (ref "X8") (pin "7") (pinfunction "F_7") (pintype "passive"))
    )
    (net (code "131") (name "unconnected-(X8H-F-Pad8)") (class "Default")
      (node (ref "X8") (pin "8") (pinfunction "F_8") (pintype "passive"))
    )
    (net (code "132") (name "unconnected-(X8I-F-Pad9)") (class "Default")
      (node (ref "X8") (pin "9") (pinfunction "F_9") (pintype "passive"))
    )
  )
)
